# mains_module.net
KiCad netlist of a schematic drawn in EAGLE
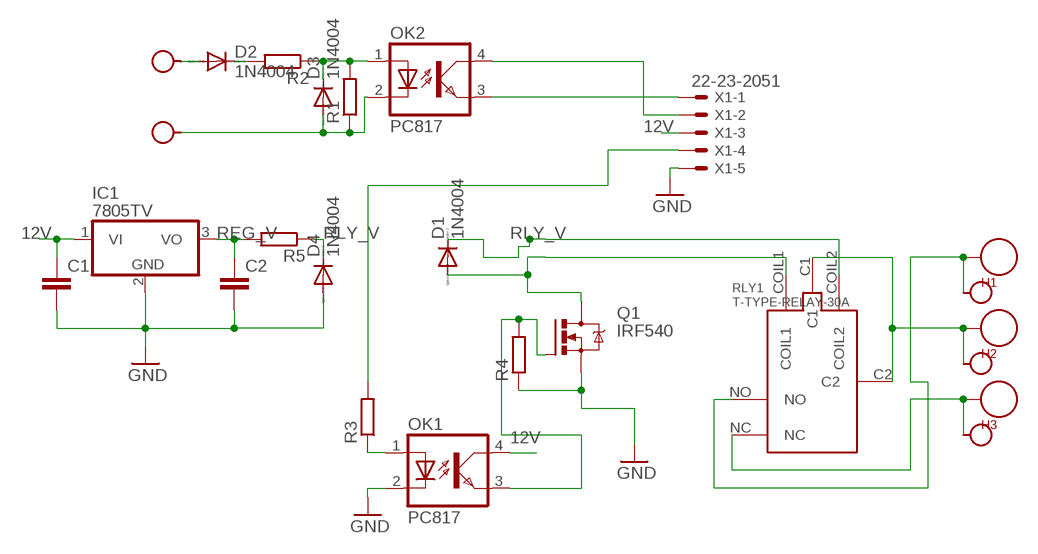
[diagram p0: schematic, sheet 1]

(export (version "E")
  (design (tool "Eeschema 10.0.6"))
  (components
    (comp (ref "C1")
      (value "C2,5-3")
      (footprint "eagle-import:C2.5-3")
      (libsource (lib "eagle-import") (part "C2,5-3"))
    )
    (comp (ref "C2")
      (value "C2,5-3")
      (footprint "eagle-import:C2.5-3")
      (libsource (lib "eagle-import") (part "C2,5-3"))
    )
    (comp (ref "D1")
      (value "1N4004")
      (footprint "eagle-import:DO41-10")
      (libsource (lib "eagle-import") (part "1N4004"))
    )
    (comp (ref "D2")
      (value "1N4004")
      (footprint "eagle-import:DO41-10")
      (libsource (lib "eagle-import") (part "1N4004"))
    )
    (comp (ref "D3")
      (value "1N4004")
      (footprint "eagle-import:DO41-10")
      (libsource (lib "eagle-import") (part "1N4004"))
    )
    (comp (ref "D4")
      (value "1N4004")
      (footprint "eagle-import:DO41-10")
      (libsource (lib "eagle-import") (part "1N4004"))
    )
    (comp (ref "H1")
      (value "SEW_HOLE")
      (footprint "eagle-import:SIMPLE_HOLE")
      (libsource (lib "eagle-import") (part "SEW_HOLE"))
    )
    (comp (ref "H2")
      (value "SEW_HOLE")
      (footprint "eagle-import:SIMPLE_HOLE")
      (libsource (lib "eagle-import") (part "SEW_HOLE"))
    )
    (comp (ref "H3")
      (value "SEW_HOLE")
      (footprint "eagle-import:SIMPLE_HOLE")
      (libsource (lib "eagle-import") (part "SEW_HOLE"))
    )
    (comp (ref "H4")
      (value "SEW_HOLE-SMALL")
      (footprint "eagle-import:SIMPLE_HOLE_SM")
      (libsource (lib "eagle-import") (part "SEW_HOLE-SMALL"))
    )
    (comp (ref "H5")
      (value "SEW_HOLE-SMALL")
      (footprint "eagle-import:SIMPLE_HOLE_SM")
      (libsource (lib "eagle-import") (part "SEW_HOLE-SMALL"))
    )
    (comp (ref "H6")
      (value "SEW_HOLE-SMALL")
      (footprint "eagle-import:SIMPLE_HOLE_SM")
      (libsource (lib "eagle-import") (part "SEW_HOLE-SMALL"))
    )
    (comp (ref "H7")
      (value "SEW_HOLE-SMALL")
      (footprint "eagle-import:SIMPLE_HOLE_SM")
      (libsource (lib "eagle-import") (part "SEW_HOLE-SMALL"))
    )
    (comp (ref "H8")
      (value "SEW_HOLE-SMALL")
      (footprint "eagle-import:SIMPLE_HOLE_SM")
      (libsource (lib "eagle-import") (part "SEW_HOLE-SMALL"))
    )
    (comp (ref "IC1")
      (value "7805TV")
      (footprint "eagle-import:TO220V")
      (libsource (lib "eagle-import") (part "78TV05"))
    )
    (comp (ref "OK1")
      (value "PC817")
      (footprint "eagle-import:DIL04")
      (fields (field (name "MPN") "PC817X4J000F"))
      (libsource (lib "eagle-import") (part "PC817"))
    )
    (comp (ref "OK2")
      (value "PC817")
      (footprint "eagle-import:DIL04")
      (fields (field (name "MPN") "PC817X4J000F"))
      (libsource (lib "eagle-import") (part "PC817"))
    )
    (comp (ref "Q1")
      (value "IRF540")
      (footprint "eagle-import:TO220BV")
      (libsource (lib "eagle-import") (part "IRF540"))
    )
    (comp (ref "R1")
      (value "R-EU_0207/7")
      (footprint "eagle-import:0207_7")
      (libsource (lib "eagle-import") (part "R-EU_0207/7"))
    )
    (comp (ref "R2")
      (value "R-EU_0207/7")
      (footprint "eagle-import:0207_7")
      (libsource (lib "eagle-import") (part "R-EU_0207/7"))
    )
    (comp (ref "R3")
      (value "R-EU_0207/7")
      (footprint "eagle-import:0207_7")
      (libsource (lib "eagle-import") (part "R-EU_0207/7"))
    )
    (comp (ref "R4")
      (value "R-EU_0207/7")
      (footprint "eagle-import:0207_7")
      (libsource (lib "eagle-import") (part "R-EU_0207/7"))
    )
    (comp (ref "R5")
      (value "R-EU_0207/7")
      (footprint "eagle-import:0207_7")
      (libsource (lib "eagle-import") (part "R-EU_0207/7"))
    )
    (comp (ref "RLY1")
      (value "T-TYPE-RELAY-30A")
      (footprint "eagle-import:T-TYPE-RELAY-30A")
      (libsource (lib "eagle-import") (part "T-TYPE-RELAY-30A"))
    )
    (comp (ref "X1")
      (value "22-23-2051")
      (footprint "eagle-import:22-23-2051")
      (fields (field (name "MF") "MOLEX"))
      (libsource (lib "eagle-import") (part "22-23-2051"))
    )
  )
  (nets
    (net (code "1") (name "/12V") (class "Default")
      (node (ref "C1") (pin "1") (pinfunction "1_1") (pintype "passive"))
      (node (ref "IC1") (pin "1") (pinfunction "VI_1") (pintype "input"))
      (node (ref "OK1") (pin "4") (pinfunction "COL_4") (pintype "passive"))
      (node (ref "X1") (pin "3") (pinfunction "S_3") (pintype "passive"))
    )
    (net (code "2") (name "/REG_V") (class "Default")
      (node (ref "C2") (pin "1") (pinfunction "1_1") (pintype "passive"))
      (node (ref "IC1") (pin "3") (pinfunction "VO_3") (pintype "passive"))
      (node (ref "R5") (pin "2") (pinfunction "2_2") (pintype "passive"))
    )
    (net (code "3") (name "/RLY_V") (class "Default")
      (node (ref "D1") (pin "C") (pinfunction "C_C") (pintype "passive"))
      (node (ref "D4") (pin "C") (pinfunction "C_C") (pintype "passive"))
      (node (ref "R5") (pin "1") (pinfunction "1_1") (pintype "passive"))
      (node (ref "RLY1") (pin "COIL2") (pinfunction "COIL2_COIL2") (pintype "bidirectional"))
    )
    (net (code "4") (name "GND") (class "Default")
      (node (ref "C1") (pin "2") (pinfunction "2_2") (pintype "passive"))
      (node (ref "C2") (pin "2") (pinfunction "2_2") (pintype "passive"))
      (node (ref "D4") (pin "A") (pinfunction "A_A") (pintype "passive"))
      (node (ref "IC1") (pin "2") (pinfunction "GND_2") (pintype "passive"))
      (node (ref "OK1") (pin "2") (pinfunction "C_2") (pintype "passive"))
      (node (ref "Q1") (pin "S") (pinfunction "S_S") (pintype "passive"))
      (node (ref "R4") (pin "1") (pinfunction "1_1") (pintype "passive"))
      (node (ref "X1") (pin "5") (pinfunction "S_5") (pintype "passive"))
    )
    (net (code "5") (name "Net-(D1-PadA)") (class "Default")
      (node (ref "D1") (pin "A") (pinfunction "A_A") (pintype "passive"))
      (node (ref "Q1") (pin "D") (pinfunction "D_D") (pintype "passive"))
      (node (ref "RLY1") (pin "COIL1") (pinfunction "COIL1_COIL1") (pintype "bidirectional"))
    )
    (net (code "6") (name "Net-(D2-PadA)") (class "Default")
      (node (ref "D2") (pin "A") (pinfunction "A_A") (pintype "passive"))
      (node (ref "H8") (pin "P$1") (pinfunction "P$1_P$1") (pintype "bidirectional"))
    )
    (net (code "7") (name "Net-(D2-PadC)") (class "Default")
      (node (ref "D2") (pin "C") (pinfunction "C_C") (pintype "passive"))
      (node (ref "R2") (pin "2") (pinfunction "2_2") (pintype "passive"))
    )
    (net (code "8") (name "Net-(H1-PadP$1)") (class "Default")
      (node (ref "H1") (pin "P$1") (pinfunction "P$1_P$1") (pintype "bidirectional"))
      (node (ref "H4") (pin "P$1") (pinfunction "P$1_P$1") (pintype "bidirectional"))
      (node (ref "RLY1") (pin "NO") (pinfunction "NO_NO") (pintype "bidirectional"))
    )
    (net (code "9") (name "Net-(H2-PadP$1)") (class "Default")
      (node (ref "H2") (pin "P$1") (pinfunction "P$1_P$1") (pintype "bidirectional"))
      (node (ref "H5") (pin "P$1") (pinfunction "P$1_P$1") (pintype "bidirectional"))
      (node (ref "RLY1") (pin "C1") (pinfunction "C1_C1") (pintype "bidirectional"))
      (node (ref "RLY1") (pin "C2") (pinfunction "C2_C2") (pintype "bidirectional"))
    )
    (net (code "10") (name "Net-(H3-PadP$1)") (class "Default")
      (node (ref "H3") (pin "P$1") (pinfunction "P$1_P$1") (pintype "bidirectional"))
      (node (ref "H6") (pin "P$1") (pinfunction "P$1_P$1") (pintype "bidirectional"))
      (node (ref "RLY1") (pin "NC") (pinfunction "NC_NC") (pintype "bidirectional"))
    )
    (net (code "11") (name "Net-(OK1-A)") (class "Default")
      (node (ref "OK1") (pin "1") (pinfunction "A_1") (pintype "passive"))
      (node (ref "R3") (pin "1") (pinfunction "1_1") (pintype "passive"))
    )
    (net (code "12") (name "Net-(OK1-EMIT)") (class "Default")
      (node (ref "OK1") (pin "3") (pinfunction "EMIT_3") (pintype "passive"))
      (node (ref "Q1") (pin "G") (pinfunction "G_G") (pintype "passive"))
      (node (ref "R4") (pin "2") (pinfunction "2_2") (pintype "passive"))
    )
    (net (code "13") (name "Net-(OK2-A)") (class "Default")
      (node (ref "D3") (pin "C") (pinfunction "C_C") (pintype "passive"))
      (node (ref "OK2") (pin "1") (pinfunction "A_1") (pintype "passive"))
      (node (ref "R1") (pin "2") (pinfunction "2_2") (pintype "passive"))
      (node (ref "R2") (pin "1") (pinfunction "1_1") (pintype "passive"))
    )
    (net (code "14") (name "Net-(OK2-C)") (class "Default")
      (node (ref "D3") (pin "A") (pinfunction "A_A") (pintype "passive"))
      (node (ref "H7") (pin "P$1") (pinfunction "P$1_P$1") (pintype "bidirectional"))
      (node (ref "OK2") (pin "2") (pinfunction "C_2") (pintype "passive"))
      (node (ref "R1") (pin "1") (pinfunction "1_1") (pintype "passive"))
    )
    (net (code "15") (name "Net-(OK2-COL)") (class "Default")
      (node (ref "OK2") (pin "4") (pinfunction "COL_4") (pintype "passive"))
      (node (ref "X1") (pin "2") (pinfunction "S_2") (pintype "passive"))
    )
    (net (code "16") (name "Net-(OK2-EMIT)") (class "Default")
      (node (ref "OK2") (pin "3") (pinfunction "EMIT_3") (pintype "passive"))
      (node (ref "X1") (pin "1") (pinfunction "S_1") (pintype "passive"))
    )
    (net (code "17") (name "Net-(X1D-S)") (class "Default")
      (node (ref "R3") (pin "2") (pinfunction "2_2") (pintype "passive"))
      (node (ref "X1") (pin "4") (pinfunction "S_4") (pintype "passive"))
    )
  )
)
